# racket_LED.net
KiCad netlist of a schematic drawn in EAGLE
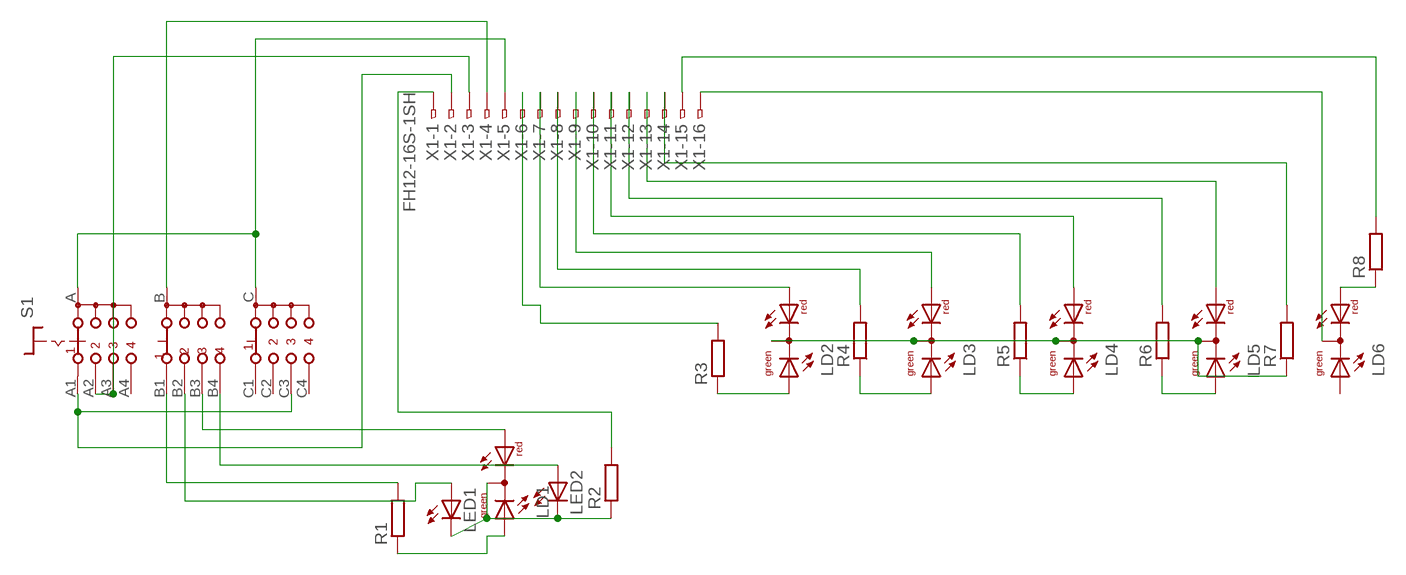
[diagram p0: schematic, sheet 1]

(export (version "E")
  (design (tool "Eeschema 10.0.6"))
  (components
    (comp (ref "LD1")
      (value "DUOLED-RG-C")
      (footprint "eagle-import:DUOLED-C-5MM")
      (libsource (lib "eagle-import") (part "DUOLED-RG-C"))
    )
    (comp (ref "LD2")
      (value "DUOLED-RG-C")
      (footprint "eagle-import:DUOLED-C-5MM")
      (libsource (lib "eagle-import") (part "DUOLED-RG-C"))
    )
    (comp (ref "LD3")
      (value "DUOLED-RG-C")
      (footprint "eagle-import:DUOLED-C-5MM")
      (libsource (lib "eagle-import") (part "DUOLED-RG-C"))
    )
    (comp (ref "LD4")
      (value "DUOLED-RG-C")
      (footprint "eagle-import:DUOLED-C-5MM")
      (libsource (lib "eagle-import") (part "DUOLED-RG-C"))
    )
    (comp (ref "LD5")
      (value "DUOLED-RG-C")
      (footprint "eagle-import:DUOLED-C-5MM")
      (libsource (lib "eagle-import") (part "DUOLED-RG-C"))
    )
    (comp (ref "LD6")
      (value "DUOLED-RG-C")
      (footprint "eagle-import:DUOLED-C-5MM")
      (libsource (lib "eagle-import") (part "DUOLED-RG-C"))
    )
    (comp (ref "LED1")
      (value "LED3MM")
      (footprint "eagle-import:LED3MM")
      (libsource (lib "eagle-import") (part "LED3MM"))
    )
    (comp (ref "LED2")
      (value "LED3MM")
      (footprint "eagle-import:LED3MM")
      (libsource (lib "eagle-import") (part "LED3MM"))
    )
    (comp (ref "R1")
      (value "R-EU_M1206")
      (footprint "eagle-import:M1206")
      (libsource (lib "eagle-import") (part "R-EU_M1206"))
    )
    (comp (ref "R2")
      (value "R-EU_M1206")
      (footprint "eagle-import:M1206")
      (libsource (lib "eagle-import") (part "R-EU_M1206"))
    )
    (comp (ref "R3")
      (value "R-EU_M1206")
      (footprint "eagle-import:M1206")
      (libsource (lib "eagle-import") (part "R-EU_M1206"))
    )
    (comp (ref "R4")
      (value "R-EU_M1206")
      (footprint "eagle-import:M1206")
      (libsource (lib "eagle-import") (part "R-EU_M1206"))
    )
    (comp (ref "R5")
      (value "R-EU_M1206")
      (footprint "eagle-import:M1206")
      (libsource (lib "eagle-import") (part "R-EU_M1206"))
    )
    (comp (ref "R6")
      (value "R-EU_M1206")
      (footprint "eagle-import:M1206")
      (libsource (lib "eagle-import") (part "R-EU_M1206"))
    )
    (comp (ref "R7")
      (value "R-EU_M1206")
      (footprint "eagle-import:M1206")
      (libsource (lib "eagle-import") (part "R-EU_M1206"))
    )
    (comp (ref "R8")
      (value "R-EU_M1206")
      (footprint "eagle-import:M1206")
      (libsource (lib "eagle-import") (part "R-EU_M1206"))
    )
    (comp (ref "S1")
      (value "CK103X04")
      (footprint "eagle-import:CK103X04")
      (libsource (lib "eagle-import") (part "CK103X04"))
    )
    (comp (ref "X1")
      (value "FH12-16S-1SH")
      (footprint "eagle-import:FH12-16S-1SH")
      (libsource (lib "eagle-import") (part "FH12-16S-1SH"))
    )
  )
  (nets
    (net (code "1") (name "Net-(LD1-AG)") (class "Default")
      (node (ref "LD1") (pin "AX") (pinfunction "AG_AX") (pintype "passive"))
      (node (ref "R1") (pin "1") (pinfunction "1_1") (pintype "passive"))
    )
    (net (code "2") (name "Net-(LD1-PadAR)") (class "Default")
      (node (ref "LD1") (pin "AR") (pinfunction "AR_AR") (pintype "passive"))
      (node (ref "S1") (pin "B3") (pinfunction "B3_B3") (pintype "passive"))
    )
    (net (code "3") (name "Net-(LD2-AG)") (class "Default")
      (node (ref "LD2") (pin "AX") (pinfunction "AG_AX") (pintype "passive"))
      (node (ref "R3") (pin "1") (pinfunction "1_1") (pintype "passive"))
    )
    (net (code "4") (name "Net-(LD2-PadC)") (class "Default")
      (node (ref "LD2") (pin "C") (pinfunction "C_C") (pintype "passive"))
      (node (ref "LD3") (pin "C") (pinfunction "C_C") (pintype "passive"))
      (node (ref "LD4") (pin "C") (pinfunction "C_C") (pintype "passive"))
      (node (ref "LD5") (pin "C") (pinfunction "C_C") (pintype "passive"))
      (node (ref "R7") (pin "1") (pinfunction "1_1") (pintype "passive"))
    )
    (net (code "5") (name "Net-(LD3-AG)") (class "Default")
      (node (ref "LD3") (pin "AX") (pinfunction "AG_AX") (pintype "passive"))
      (node (ref "R4") (pin "1") (pinfunction "1_1") (pintype "passive"))
    )
    (net (code "6") (name "Net-(LD4-AG)") (class "Default")
      (node (ref "LD4") (pin "AX") (pinfunction "AG_AX") (pintype "passive"))
      (node (ref "R5") (pin "1") (pinfunction "1_1") (pintype "passive"))
    )
    (net (code "7") (name "Net-(LD5-AG)") (class "Default")
      (node (ref "LD5") (pin "AX") (pinfunction "AG_AX") (pintype "passive"))
      (node (ref "R6") (pin "1") (pinfunction "1_1") (pintype "passive"))
    )
    (net (code "8") (name "Net-(LD6-PadAR)") (class "Default")
      (node (ref "LD6") (pin "AR") (pinfunction "AR_AR") (pintype "passive"))
      (node (ref "R8") (pin "1") (pinfunction "1_1") (pintype "passive"))
    )
    (net (code "9") (name "Net-(LED1-C)") (class "Default")
      (node (ref "LD1") (pin "C") (pinfunction "C_C") (pintype "passive"))
      (node (ref "LED1") (pin "K") (pinfunction "C_K") (pintype "passive"))
      (node (ref "LED2") (pin "K") (pinfunction "C_K") (pintype "passive"))
      (node (ref "R2") (pin "1") (pinfunction "1_1") (pintype "passive"))
    )
    (net (code "10") (name "Net-(LED1-PadA)") (class "Default")
      (node (ref "LED1") (pin "A") (pinfunction "A_A") (pintype "passive"))
      (node (ref "S1") (pin "B2") (pinfunction "B2_B2") (pintype "passive"))
    )
    (net (code "11") (name "Net-(LED2-PadA)") (class "Default")
      (node (ref "LED2") (pin "A") (pinfunction "A_A") (pintype "passive"))
      (node (ref "S1") (pin "B4") (pinfunction "B4_B4") (pintype "passive"))
    )
    (net (code "12") (name "Net-(R1-Pad2)") (class "Default")
      (node (ref "R1") (pin "2") (pinfunction "2_2") (pintype "passive"))
      (node (ref "S1") (pin "B1") (pinfunction "B1_B1") (pintype "passive"))
    )
    (net (code "13") (name "Net-(R2-Pad2)") (class "Default")
      (node (ref "R2") (pin "2") (pinfunction "2_2") (pintype "passive"))
      (node (ref "X1") (pin "1") (pinfunction "1_1") (pintype "passive"))
    )
    (net (code "14") (name "Net-(X1B-1)") (class "Default")
      (node (ref "R5") (pin "2") (pinfunction "2_2") (pintype "passive"))
      (node (ref "X1") (pin "10") (pinfunction "1_10") (pintype "passive"))
    )
    (net (code "15") (name "Net-(X1C-1)") (class "Default")
      (node (ref "LD4") (pin "AR") (pinfunction "AR_AR") (pintype "passive"))
      (node (ref "X1") (pin "11") (pinfunction "1_11") (pintype "passive"))
    )
    (net (code "16") (name "Net-(X1D-1)") (class "Default")
      (node (ref "R6") (pin "2") (pinfunction "2_2") (pintype "passive"))
      (node (ref "X1") (pin "12") (pinfunction "1_12") (pintype "passive"))
    )
    (net (code "17") (name "Net-(X1E-1)") (class "Default")
      (node (ref "LD5") (pin "AR") (pinfunction "AR_AR") (pintype "passive"))
      (node (ref "X1") (pin "13") (pinfunction "1_13") (pintype "passive"))
    )
    (net (code "18") (name "Net-(X1F-1)") (class "Default")
      (node (ref "R7") (pin "2") (pinfunction "2_2") (pintype "passive"))
      (node (ref "X1") (pin "14") (pinfunction "1_14") (pintype "passive"))
    )
    (net (code "19") (name "Net-(X1G-1)") (class "Default")
      (node (ref "R8") (pin "2") (pinfunction "2_2") (pintype "passive"))
      (node (ref "X1") (pin "15") (pinfunction "1_15") (pintype "passive"))
    )
    (net (code "20") (name "Net-(X1H-1)") (class "Default")
      (node (ref "LD6") (pin "C") (pinfunction "C_C") (pintype "passive"))
      (node (ref "X1") (pin "16") (pinfunction "1_16") (pintype "passive"))
    )
    (net (code "21") (name "Net-(X1I-1)") (class "Default")
      (node (ref "S1") (pin "A1") (pinfunction "A1_A1") (pintype "passive"))
      (node (ref "S1") (pin "C3") (pinfunction "C3_C3") (pintype "passive"))
      (node (ref "X1") (pin "2") (pinfunction "1_2") (pintype "passive"))
    )
    (net (code "22") (name "Net-(X1J-1)") (class "Default")
      (node (ref "S1") (pin "A2") (pinfunction "A2_A2") (pintype "passive"))
      (node (ref "S1") (pin "A3") (pinfunction "A3_A3") (pintype "passive"))
      (node (ref "X1") (pin "3") (pinfunction "1_3") (pintype "passive"))
    )
    (net (code "23") (name "Net-(X1K-1)") (class "Default")
      (node (ref "S1") (pin "B") (pinfunction "B_B") (pintype "passive"))
      (node (ref "X1") (pin "4") (pinfunction "1_4") (pintype "passive"))
    )
    (net (code "24") (name "Net-(X1L-1)") (class "Default")
      (node (ref "S1") (pin "A") (pinfunction "A_A") (pintype "passive"))
      (node (ref "S1") (pin "C") (pinfunction "C_C") (pintype "passive"))
      (node (ref "X1") (pin "5") (pinfunction "1_5") (pintype "passive"))
    )
    (net (code "25") (name "Net-(X1M-1)") (class "Default")
      (node (ref "R3") (pin "2") (pinfunction "2_2") (pintype "passive"))
      (node (ref "X1") (pin "6") (pinfunction "1_6") (pintype "passive"))
    )
    (net (code "26") (name "Net-(X1N-1)") (class "Default")
      (node (ref "LD2") (pin "AR") (pinfunction "AR_AR") (pintype "passive"))
      (node (ref "X1") (pin "7") (pinfunction "1_7") (pintype "passive"))
    )
    (net (code "27") (name "Net-(X1O-1)") (class "Default")
      (node (ref "R4") (pin "2") (pinfunction "2_2") (pintype "passive"))
      (node (ref "X1") (pin "8") (pinfunction "1_8") (pintype "passive"))
    )
    (net (code "28") (name "Net-(X1P-1)") (class "Default")
      (node (ref "LD3") (pin "AR") (pinfunction "AR_AR") (pintype "passive"))
      (node (ref "X1") (pin "9") (pinfunction "1_9") (pintype "passive"))
    )
    (net (code "29") (name "unconnected-(LD6-AG-PadAX)") (class "Default")
      (node (ref "LD6") (pin "AX") (pinfunction "AG_AX") (pintype "passive"))
    )
    (net (code "30") (name "unconnected-(S1-PadA4)") (class "Default")
      (node (ref "S1") (pin "A4") (pinfunction "A4_A4") (pintype "passive"))
    )
    (net (code "31") (name "unconnected-(S1-PadC1)") (class "Default")
      (node (ref "S1") (pin "C1") (pinfunction "C1_C1") (pintype "passive"))
    )
    (net (code "32") (name "unconnected-(S1-PadC2)") (class "Default")
      (node (ref "S1") (pin "C2") (pinfunction "C2_C2") (pintype "passive"))
    )
    (net (code "33") (name "unconnected-(S1-PadC4)") (class "Default")
      (node (ref "S1") (pin "C4") (pinfunction "C4_C4") (pintype "passive"))
    )
  )
)
